# nintendo-hid.net
KiCad netlist of a schematic drawn in EAGLE
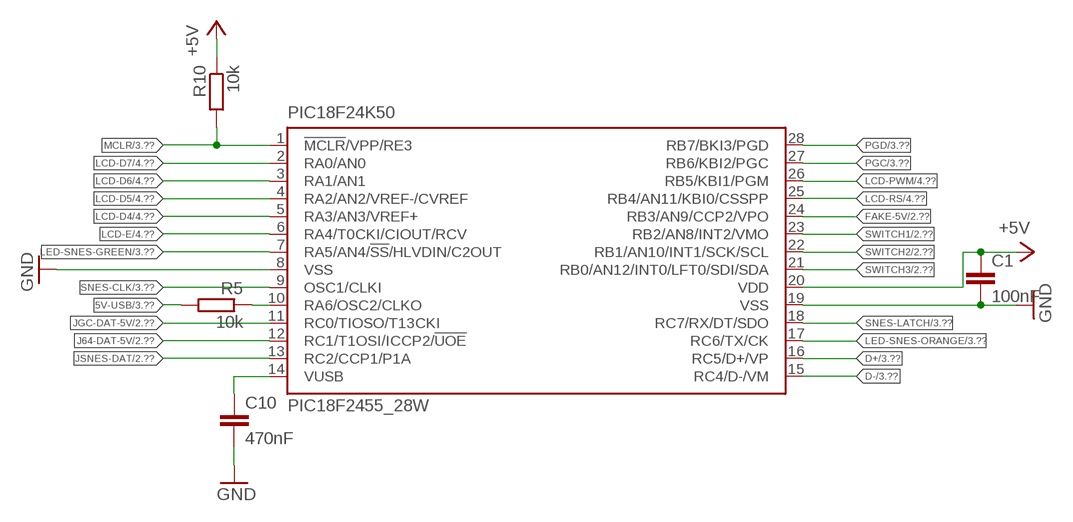
[diagram p0: schematic, sheet 1]
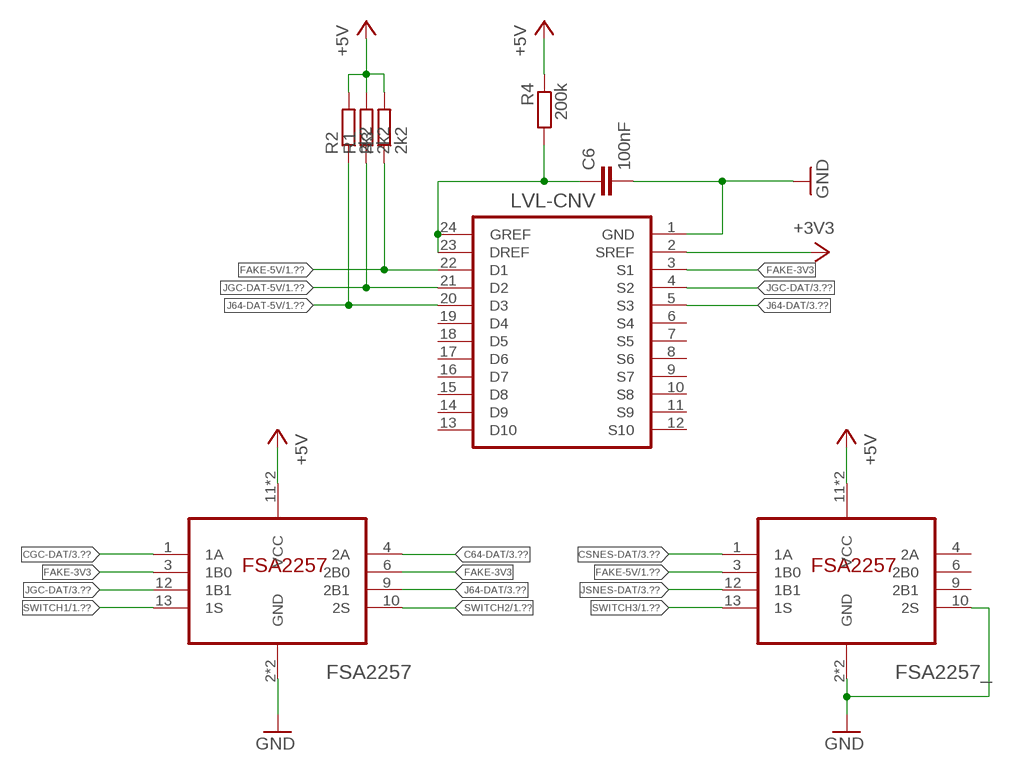
[diagram p1: schematic, sheet 2]
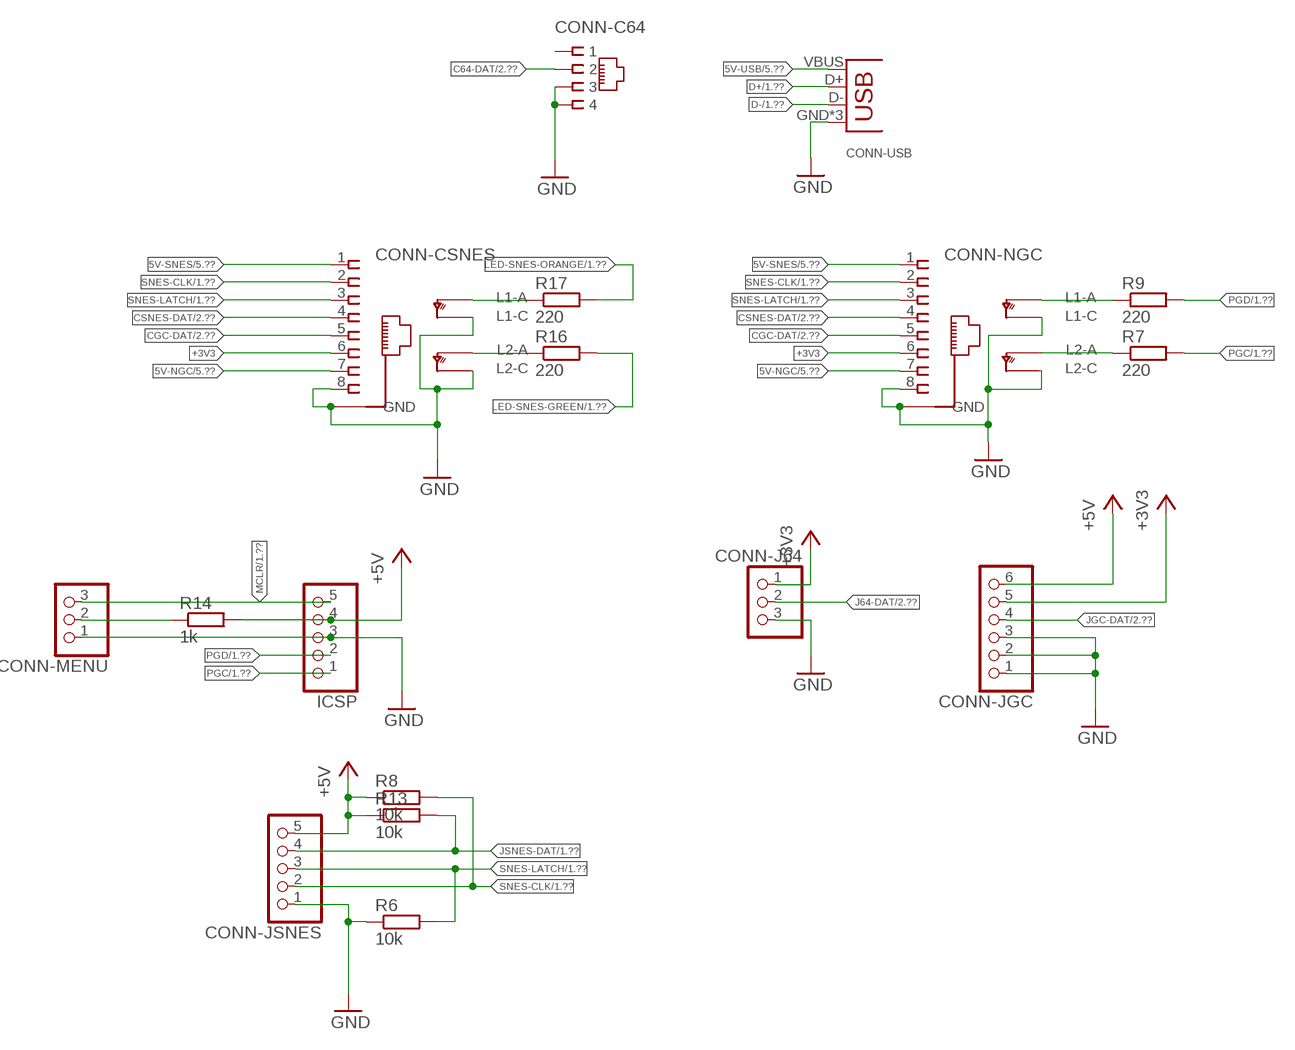
[diagram p2: schematic, sheet 3]
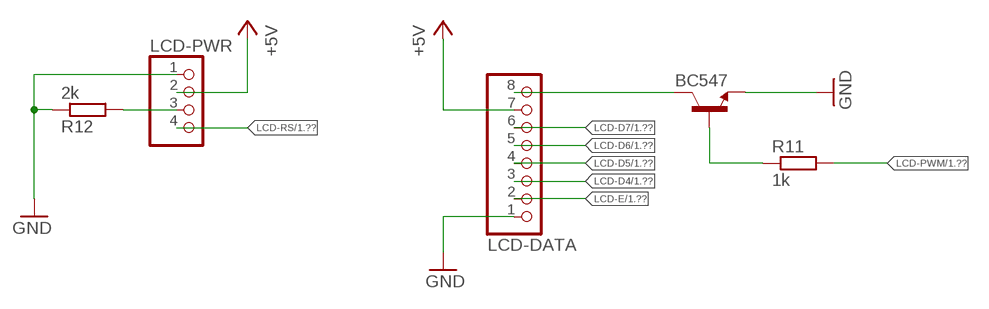
[diagram p3: schematic, sheet 4]
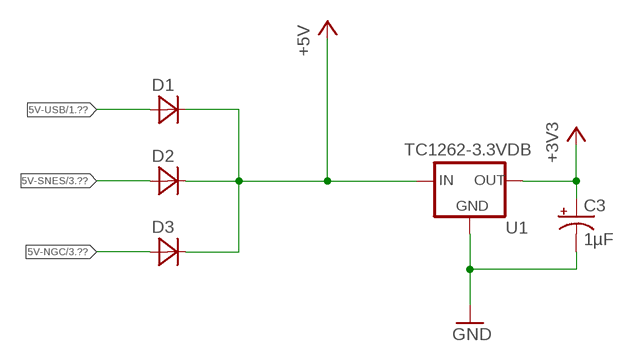
[diagram p4: schematic, sheet 5]

(export (version "E")
  (design (tool "Eeschema 10.0.6"))
  (components
    (comp (ref "CONN-C64")
      (value "RJ11-6P4C")
      (footprint "eagle-import:RJ11-4C")
      (libsource (lib "eagle-import") (part "RJ11-6P4C"))
    )
    (comp (ref "CONN-CSNES")
      (value "RJ45-NIELS")
      (footprint "eagle-import:RJ45-NIELS")
      (libsource (lib "eagle-import") (part "RJ45-NIELS"))
    )
    (comp (ref "CONN-J64")
      (value "PINHD-1X3")
      (footprint "eagle-import:1X03")
      (libsource (lib "eagle-import") (part "PINHD-1X3"))
    )
    (comp (ref "CONN-JGC")
      (value "PINHD-1X6")
      (footprint "eagle-import:1X06")
      (libsource (lib "eagle-import") (part "PINHD-1X6"))
    )
    (comp (ref "CONN-JSNES")
      (value "PINHD-1X5")
      (footprint "eagle-import:1X05")
      (libsource (lib "eagle-import") (part "PINHD-1X5"))
    )
    (comp (ref "CONN-MENU")
      (value "PINHD-1X3")
      (footprint "eagle-import:1X03")
      (libsource (lib "eagle-import") (part "PINHD-1X3"))
    )
    (comp (ref "CONN-NGC")
      (value "RJ45-NIELS")
      (footprint "eagle-import:RJ45-NIELS")
      (libsource (lib "eagle-import") (part "RJ45-NIELS"))
    )
    (comp (ref "CONN-USB")
      (value "USB-B-NIELS")
      (footprint "eagle-import:USB-B-H")
      (libsource (lib "eagle-import") (part "USB-B-NIELS"))
    )
    (comp (ref "ICSP")
      (value "PINHD-1X5")
      (footprint "eagle-import:1X05")
      (libsource (lib "eagle-import") (part "PINHD-1X5"))
    )
    (comp (ref "R6")
      (value "10k")
      (footprint "eagle-import:R0603")
      (libsource (lib "eagle-import") (part "R-EU_R0603"))
    )
    (comp (ref "R7")
      (value "220")
      (footprint "eagle-import:R0603")
      (libsource (lib "eagle-import") (part "R-EU_R0603"))
    )
    (comp (ref "R8")
      (value "10k")
      (footprint "eagle-import:R0603")
      (libsource (lib "eagle-import") (part "R-EU_R0603"))
    )
    (comp (ref "R9")
      (value "220")
      (footprint "eagle-import:R0603")
      (libsource (lib "eagle-import") (part "R-EU_R0603"))
    )
    (comp (ref "R13")
      (value "10k")
      (footprint "eagle-import:R0603")
      (libsource (lib "eagle-import") (part "R-EU_R0603"))
    )
    (comp (ref "R14")
      (value "1k")
      (footprint "eagle-import:R0603")
      (libsource (lib "eagle-import") (part "R-EU_R0603"))
    )
    (comp (ref "R16")
      (value "220")
      (footprint "eagle-import:R0603")
      (libsource (lib "eagle-import") (part "R-EU_R0603"))
    )
    (comp (ref "R17")
      (value "220")
      (footprint "eagle-import:R0603")
      (libsource (lib "eagle-import") (part "R-EU_R0603"))
    )
    (comp (ref "C1")
      (value "100nF")
      (footprint "eagle-import:C0603")
      (libsource (lib "eagle-import") (part "C-EUC0603"))
    )
    (comp (ref "C10")
      (value "470nF")
      (footprint "eagle-import:C0603")
      (libsource (lib "eagle-import") (part "C-EUC0603"))
    )
    (comp (ref "PIC18F24K50")
      (value "PIC18F2455_28W")
      (footprint "eagle-import:SO28W")
      (fields (field (name "MF") "MICROCHIP") (field (name "MPN") "PIC18F2455-I/SO"))
      (libsource (lib "eagle-import") (part "PIC18F2_28W455"))
    )
    (comp (ref "R5")
      (value "10k")
      (footprint "eagle-import:R0603")
      (libsource (lib "eagle-import") (part "R-EU_R0603"))
    )
    (comp (ref "R10")
      (value "10k")
      (footprint "eagle-import:R0603")
      (libsource (lib "eagle-import") (part "R-EU_R0603"))
    )
    (comp (ref "BC547")
      (value "BC547")
      (footprint "eagle-import:TO92")
      (libsource (lib "eagle-import") (part "BC547"))
    )
    (comp (ref "LCD-DATA")
      (value "PINHD-1X8")
      (footprint "eagle-import:1X08")
      (libsource (lib "eagle-import") (part "PINHD-1X8"))
    )
    (comp (ref "LCD-PWR")
      (value "PINHD-1X4")
      (footprint "eagle-import:1X04")
      (libsource (lib "eagle-import") (part "PINHD-1X4"))
    )
    (comp (ref "R11")
      (value "1k")
      (footprint "eagle-import:R0603")
      (libsource (lib "eagle-import") (part "R-EU_R0603"))
    )
    (comp (ref "R12")
      (value "2k")
      (footprint "eagle-import:R0603")
      (libsource (lib "eagle-import") (part "R-EU_R0603"))
    )
    (comp (ref "C6")
      (value "100nF")
      (footprint "eagle-import:C0603")
      (libsource (lib "eagle-import") (part "C-EUC0603"))
    )
    (comp (ref "FSA2257")
      (value "FSA2257MTCX")
      (footprint "eagle-import:TSSOP14")
      (libsource (lib "eagle-import") (part "FSA2257MTCX"))
    )
    (comp (ref "FSA2257_")
      (value "FSA2257MTCX")
      (footprint "eagle-import:TSSOP14")
      (libsource (lib "eagle-import") (part "FSA2257MTCX"))
    )
    (comp (ref "LVL-CNV")
      (value "GTL2010")
      (footprint "eagle-import:TSSOP24")
      (libsource (lib "eagle-import") (part "GTL2010"))
    )
    (comp (ref "R1")
      (value "2k2")
      (footprint "eagle-import:R0603")
      (libsource (lib "eagle-import") (part "R-EU_R0603"))
    )
    (comp (ref "R2")
      (value "2k2")
      (footprint "eagle-import:R0603")
      (libsource (lib "eagle-import") (part "R-EU_R0603"))
    )
    (comp (ref "R3")
      (value "2k2")
      (footprint "eagle-import:R0603")
      (libsource (lib "eagle-import") (part "R-EU_R0603"))
    )
    (comp (ref "R4")
      (value "200k")
      (footprint "eagle-import:R0603")
      (libsource (lib "eagle-import") (part "R-EU_R0603"))
    )
    (comp (ref "C3")
      (value "1µF")
      (footprint "eagle-import:PANASONIC_D")
      (libsource (lib "eagle-import") (part "47UF-50V-20%(ELECT)"))
    )
    (comp (ref "D1")
      (value "MBR120VLSFT1G")
      (footprint "eagle-import:SOD123")
      (libsource (lib "eagle-import") (part "MBR120VLSFT1G"))
    )
    (comp (ref "D2")
      (value "MBR120VLSFT1G")
      (footprint "eagle-import:SOD123")
      (libsource (lib "eagle-import") (part "MBR120VLSFT1G"))
    )
    (comp (ref "D3")
      (value "MBR120VLSFT1G")
      (footprint "eagle-import:SOD123")
      (libsource (lib "eagle-import") (part "MBR120VLSFT1G"))
    )
    (comp (ref "U1")
      (value "TC1262-3.3VDB")
      (footprint "eagle-import:SOT230P700X180-4N")
      (libsource (lib "eagle-import") (part "TC1262-3.3VDB"))
    )
  )
  (nets
    (net (code "1") (name "+3V3") (class "Default")
      (node (ref "C3") (pin "+") (pinfunction "+_+") (pintype "passive"))
      (node (ref "CONN-CSNES") (pin "6") (pinfunction "6_6") (pintype "passive"))
      (node (ref "CONN-J64") (pin "1") (pinfunction "1_1") (pintype "passive"))
      (node (ref "CONN-JGC") (pin "5") (pinfunction "5_5") (pintype "passive"))
      (node (ref "CONN-NGC") (pin "6") (pinfunction "6_6") (pintype "passive"))
      (node (ref "LVL-CNV") (pin "2") (pinfunction "SREF_2") (pintype "power_in"))
      (node (ref "U1") (pin "3") (pinfunction "OUT_3") (pintype "passive"))
    )
    (net (code "2") (name "+5V") (class "Default")
      (node (ref "C1") (pin "1") (pinfunction "1_1") (pintype "passive"))
      (node (ref "CONN-JGC") (pin "6") (pinfunction "6_6") (pintype "passive"))
      (node (ref "CONN-JSNES") (pin "5") (pinfunction "5_5") (pintype "passive"))
      (node (ref "D1") (pin "1") (pinfunction "C_1") (pintype "passive"))
      (node (ref "D2") (pin "1") (pinfunction "C_1") (pintype "passive"))
      (node (ref "D3") (pin "1") (pinfunction "C_1") (pintype "passive"))
      (node (ref "FSA2257") (pin "11") (pinfunction "VCC_11") (pintype "power_in"))
      (node (ref "FSA2257") (pin "14") (pinfunction "VCC_14") (pintype "power_in"))
      (node (ref "FSA2257_") (pin "11") (pinfunction "VCC_11") (pintype "power_in"))
      (node (ref "FSA2257_") (pin "14") (pinfunction "VCC_14") (pintype "power_in"))
      (node (ref "ICSP") (pin "4") (pinfunction "4_4") (pintype "passive"))
      (node (ref "LCD-DATA") (pin "7") (pinfunction "7_7") (pintype "passive"))
      (node (ref "LCD-PWR") (pin "2") (pinfunction "2_2") (pintype "passive"))
      (node (ref "PIC18F24K50") (pin "20") (pinfunction "VDD_20") (pintype "power_in"))
      (node (ref "R1") (pin "2") (pinfunction "2_2") (pintype "passive"))
      (node (ref "R10") (pin "1") (pinfunction "1_1") (pintype "passive"))
      (node (ref "R13") (pin "1") (pinfunction "1_1") (pintype "passive"))
      (node (ref "R14") (pin "2") (pinfunction "2_2") (pintype "passive"))
      (node (ref "R2") (pin "2") (pinfunction "2_2") (pintype "passive"))
      (node (ref "R3") (pin "2") (pinfunction "2_2") (pintype "passive"))
      (node (ref "R4") (pin "1") (pinfunction "1_1") (pintype "passive"))
      (node (ref "R8") (pin "1") (pinfunction "1_1") (pintype "passive"))
      (node (ref "U1") (pin "1") (pinfunction "IN_1") (pintype "input"))
    )
    (net (code "3") (name "5V-NGC") (class "Default")
      (node (ref "CONN-CSNES") (pin "7") (pinfunction "7_7") (pintype "passive"))
      (node (ref "CONN-NGC") (pin "7") (pinfunction "7_7") (pintype "passive"))
      (node (ref "D3") (pin "2") (pinfunction "A_2") (pintype "passive"))
    )
    (net (code "4") (name "5V-SNES") (class "Default")
      (node (ref "CONN-CSNES") (pin "1") (pinfunction "1_1") (pintype "passive"))
      (node (ref "CONN-NGC") (pin "1") (pinfunction "1_1") (pintype "passive"))
      (node (ref "D2") (pin "2") (pinfunction "A_2") (pintype "passive"))
    )
    (net (code "5") (name "5V-USB") (class "Default")
      (node (ref "CONN-USB") (pin "VBUS") (pinfunction "VBUS_VBUS") (pintype "bidirectional"))
      (node (ref "D1") (pin "2") (pinfunction "A_2") (pintype "passive"))
      (node (ref "R5") (pin "2") (pinfunction "2_2") (pintype "passive"))
    )
    (net (code "6") (name "C64-DAT") (class "Default")
      (node (ref "CONN-C64") (pin "2") (pinfunction "2_2") (pintype "passive"))
      (node (ref "FSA2257") (pin "4") (pinfunction "2A_4") (pintype "bidirectional"))
    )
    (net (code "7") (name "CGC-DAT") (class "Default")
      (node (ref "CONN-CSNES") (pin "5") (pinfunction "5_5") (pintype "passive"))
      (node (ref "CONN-NGC") (pin "5") (pinfunction "5_5") (pintype "passive"))
      (node (ref "FSA2257") (pin "1") (pinfunction "1A_1") (pintype "bidirectional"))
    )
    (net (code "8") (name "CSNES-DAT") (class "Default")
      (node (ref "CONN-CSNES") (pin "4") (pinfunction "4_4") (pintype "passive"))
      (node (ref "CONN-NGC") (pin "4") (pinfunction "4_4") (pintype "passive"))
      (node (ref "FSA2257_") (pin "1") (pinfunction "1A_1") (pintype "bidirectional"))
    )
    (net (code "9") (name "D+") (class "Default")
      (node (ref "CONN-USB") (pin "D+") (pinfunction "D+_D+") (pintype "bidirectional"))
      (node (ref "PIC18F24K50") (pin "16") (pinfunction "RC5/D+/VP_16") (pintype "bidirectional"))
    )
    (net (code "10") (name "D-") (class "Default")
      (node (ref "CONN-USB") (pin "D-") (pinfunction "D-_D-") (pintype "bidirectional"))
      (node (ref "PIC18F24K50") (pin "15") (pinfunction "RC4/D-/VM_15") (pintype "bidirectional"))
    )
    (net (code "11") (name "FAKE-3V3") (class "Default")
      (node (ref "FSA2257") (pin "3") (pinfunction "1B0_3") (pintype "bidirectional"))
      (node (ref "FSA2257") (pin "6") (pinfunction "2B0_6") (pintype "bidirectional"))
      (node (ref "LVL-CNV") (pin "3") (pinfunction "S1_3") (pintype "bidirectional"))
    )
    (net (code "12") (name "FAKE-5V") (class "Default")
      (node (ref "FSA2257_") (pin "3") (pinfunction "1B0_3") (pintype "bidirectional"))
      (node (ref "LVL-CNV") (pin "22") (pinfunction "D1_22") (pintype "bidirectional"))
      (node (ref "PIC18F24K50") (pin "24") (pinfunction "RB3/AN9/CCP2/VPO_24") (pintype "bidirectional"))
      (node (ref "R3") (pin "1") (pinfunction "1_1") (pintype "passive"))
    )
    (net (code "13") (name "GND") (class "Default")
      (node (ref "BC547") (pin "1") (pinfunction "E_1") (pintype "passive"))
      (node (ref "C1") (pin "2") (pinfunction "2_2") (pintype "passive"))
      (node (ref "C10") (pin "2") (pinfunction "2_2") (pintype "passive"))
      (node (ref "C3") (pin "-") (pinfunction "-_-") (pintype "passive"))
      (node (ref "C6") (pin "2") (pinfunction "2_2") (pintype "passive"))
      (node (ref "CONN-C64") (pin "3") (pinfunction "3_3") (pintype "passive"))
      (node (ref "CONN-C64") (pin "4") (pinfunction "4_4") (pintype "passive"))
      (node (ref "CONN-CSNES") (pin "8") (pinfunction "8_8") (pintype "passive"))
      (node (ref "CONN-CSNES") (pin "GND@5") (pinfunction "GND_GND@5") (pintype "power_in"))
      (node (ref "CONN-CSNES") (pin "GND@6") (pinfunction "GND_GND@6") (pintype "power_in"))
      (node (ref "CONN-CSNES") (pin "LED-GREEN-C") (pinfunction "L2C_LED-GREEN-C") (pintype "bidirectional"))
      (node (ref "CONN-CSNES") (pin "LED-ORANGE-C") (pinfunction "L1C_LED-ORANGE-C") (pintype "bidirectional"))
      (node (ref "CONN-J64") (pin "3") (pinfunction "3_3") (pintype "passive"))
      (node (ref "CONN-JGC") (pin "1") (pinfunction "1_1") (pintype "passive"))
      (node (ref "CONN-JGC") (pin "2") (pinfunction "2_2") (pintype "passive"))
      (node (ref "CONN-JGC") (pin "3") (pinfunction "3_3") (pintype "passive"))
      (node (ref "CONN-JSNES") (pin "1") (pinfunction "1_1") (pintype "passive"))
      (node (ref "CONN-MENU") (pin "1") (pinfunction "1_1") (pintype "passive"))
      (node (ref "CONN-NGC") (pin "8") (pinfunction "8_8") (pintype "passive"))
      (node (ref "CONN-NGC") (pin "GND@5") (pinfunction "GND_GND@5") (pintype "power_in"))
      (node (ref "CONN-NGC") (pin "GND@6") (pinfunction "GND_GND@6") (pintype "power_in"))
      (node (ref "CONN-NGC") (pin "LED-GREEN-C") (pinfunction "L2C_LED-GREEN-C") (pintype "bidirectional"))
      (node (ref "CONN-NGC") (pin "LED-ORANGE-C") (pinfunction "L1C_LED-ORANGE-C") (pintype "bidirectional"))
      (node (ref "CONN-USB") (pin "GND") (pinfunction "GND_GND") (pintype "bidirectional"))
      (node (ref "CONN-USB") (pin "GND@1") (pinfunction "GND_GND@1") (pintype "bidirectional"))
      (node (ref "CONN-USB") (pin "GND@2") (pinfunction "GND_GND@2") (pintype "bidirectional"))
      (node (ref "FSA2257") (pin "2") (pinfunction "GND_2") (pintype "power_in"))
      (node (ref "FSA2257") (pin "5") (pinfunction "GND_5") (pintype "power_in"))
      (node (ref "FSA2257_") (pin "10") (pinfunction "2S_10") (pintype "input"))
      (node (ref "FSA2257_") (pin "2") (pinfunction "GND_2") (pintype "power_in"))
      (node (ref "FSA2257_") (pin "5") (pinfunction "GND_5") (pintype "power_in"))
      (node (ref "ICSP") (pin "3") (pinfunction "3_3") (pintype "passive"))
      (node (ref "LCD-DATA") (pin "1") (pinfunction "1_1") (pintype "passive"))
      (node (ref "LCD-PWR") (pin "1") (pinfunction "1_1") (pintype "passive"))
      (node (ref "LVL-CNV") (pin "1") (pinfunction "GND_1") (pintype "power_in"))
      (node (ref "PIC18F24K50") (pin "19") (pinfunction "VSS_19") (pintype "power_in"))
      (node (ref "PIC18F24K50") (pin "8") (pinfunction "VSS_8") (pintype "power_in"))
      (node (ref "R12") (pin "1") (pinfunction "1_1") (pintype "passive"))
      (node (ref "R6") (pin "1") (pinfunction "1_1") (pintype "passive"))
      (node (ref "U1") (pin "2") (pinfunction "GND_2") (pintype "input"))
      (node (ref "U1") (pin "4") (pinfunction "GND_4") (pintype "input"))
    )
    (net (code "14") (name "J64-DAT") (class "Default")
      (node (ref "CONN-J64") (pin "2") (pinfunction "2_2") (pintype "passive"))
      (node (ref "FSA2257") (pin "9") (pinfunction "2B1_9") (pintype "bidirectional"))
      (node (ref "LVL-CNV") (pin "5") (pinfunction "S3_5") (pintype "bidirectional"))
    )
    (net (code "15") (name "J64-DAT-5V") (class "Default")
      (node (ref "LVL-CNV") (pin "20") (pinfunction "D3_20") (pintype "bidirectional"))
      (node (ref "PIC18F24K50") (pin "12") (pinfunction "RC1/T1OSI/ICCP2/~{UOE}_12") (pintype "bidirectional"))
      (node (ref "R2") (pin "1") (pinfunction "1_1") (pintype "passive"))
    )
    (net (code "16") (name "JGC-DAT") (class "Default")
      (node (ref "CONN-JGC") (pin "4") (pinfunction "4_4") (pintype "passive"))
      (node (ref "FSA2257") (pin "12") (pinfunction "1B1_12") (pintype "bidirectional"))
      (node (ref "LVL-CNV") (pin "4") (pinfunction "S2_4") (pintype "bidirectional"))
    )
    (net (code "17") (name "JGC-DAT-5V") (class "Default")
      (node (ref "LVL-CNV") (pin "21") (pinfunction "D2_21") (pintype "bidirectional"))
      (node (ref "PIC18F24K50") (pin "11") (pinfunction "RC0/TIOSO/T13CKI_11") (pintype "bidirectional"))
      (node (ref "R1") (pin "1") (pinfunction "1_1") (pintype "passive"))
    )
    (net (code "18") (name "JSNES-DAT") (class "Default")
      (node (ref "CONN-JSNES") (pin "4") (pinfunction "4_4") (pintype "passive"))
      (node (ref "FSA2257_") (pin "12") (pinfunction "1B1_12") (pintype "bidirectional"))
      (node (ref "PIC18F24K50") (pin "13") (pinfunction "RC2/CCP1/P1A_13") (pintype "bidirectional"))
      (node (ref "R13") (pin "2") (pinfunction "2_2") (pintype "passive"))
    )
    (net (code "19") (name "LCD-D4") (class "Default")
      (node (ref "LCD-DATA") (pin "3") (pinfunction "3_3") (pintype "passive"))
      (node (ref "PIC18F24K50") (pin "5") (pinfunction "RA3/AN3/VREF+_5") (pintype "bidirectional"))
    )
    (net (code "20") (name "LCD-D5") (class "Default")
      (node (ref "LCD-DATA") (pin "4") (pinfunction "4_4") (pintype "passive"))
      (node (ref "PIC18F24K50") (pin "4") (pinfunction "RA2/AN2/VREF-/CVREF_4") (pintype "bidirectional"))
    )
    (net (code "21") (name "LCD-D6") (class "Default")
      (node (ref "LCD-DATA") (pin "5") (pinfunction "5_5") (pintype "passive"))
      (node (ref "PIC18F24K50") (pin "3") (pinfunction "RA1/AN1_3") (pintype "bidirectional"))
    )
    (net (code "22") (name "LCD-D7") (class "Default")
      (node (ref "LCD-DATA") (pin "6") (pinfunction "6_6") (pintype "passive"))
      (node (ref "PIC18F24K50") (pin "2") (pinfunction "RA0/AN0_2") (pintype "bidirectional"))
    )
    (net (code "23") (name "LCD-E") (class "Default")
      (node (ref "LCD-DATA") (pin "2") (pinfunction "2_2") (pintype "passive"))
      (node (ref "PIC18F24K50") (pin "6") (pinfunction "RA4/T0CKI/CIOUT/RCV_6") (pintype "bidirectional"))
    )
    (net (code "24") (name "LCD-PWM") (class "Default")
      (node (ref "PIC18F24K50") (pin "26") (pinfunction "RB5/KBI1/PGM_26") (pintype "bidirectional"))
      (node (ref "R11") (pin "2") (pinfunction "2_2") (pintype "passive"))
    )
    (net (code "25") (name "LCD-RS") (class "Default")
      (node (ref "LCD-PWR") (pin "4") (pinfunction "4_4") (pintype "passive"))
      (node (ref "PIC18F24K50") (pin "25") (pinfunction "RB4/AN11/KBI0/CSSPP_25") (pintype "bidirectional"))
    )
    (net (code "26") (name "LED-SNES-GREEN") (class "Default")
      (node (ref "PIC18F24K50") (pin "7") (pinfunction "RA5/AN4/~{SS}/HLVDIN/C2OUT_7") (pintype "bidirectional"))
      (node (ref "R16") (pin "2") (pinfunction "2_2") (pintype "passive"))
    )
    (net (code "27") (name "LED-SNES-ORANGE") (class "Default")
      (node (ref "PIC18F24K50") (pin "17") (pinfunction "RC6/TX/CK_17") (pintype "bidirectional"))
      (node (ref "R17") (pin "2") (pinfunction "2_2") (pintype "passive"))
    )
    (net (code "28") (name "MCLR") (class "Default")
      (node (ref "CONN-MENU") (pin "3") (pinfunction "3_3") (pintype "passive"))
      (node (ref "ICSP") (pin "5") (pinfunction "5_5") (pintype "passive"))
      (node (ref "PIC18F24K50") (pin "1") (pinfunction "~{MCLR}/VPP/RE3_1") (pintype "input"))
      (node (ref "R10") (pin "2") (pinfunction "2_2") (pintype "passive"))
    )
    (net (code "29") (name "Net-(BC547-B)") (class "Default")
      (node (ref "BC547") (pin "2") (pinfunction "B_2") (pintype "passive"))
      (node (ref "R11") (pin "1") (pinfunction "1_1") (pintype "passive"))
    )
    (net (code "30") (name "Net-(BC547-C)") (class "Default")
      (node (ref "BC547") (pin "3") (pinfunction "C_3") (pintype "passive"))
      (node (ref "LCD-DATA") (pin "8") (pinfunction "8_8") (pintype "passive"))
    )
    (net (code "31") (name "Net-(CONN-CSNES-L1A)") (class "Default")
      (node (ref "CONN-CSNES") (pin "LED-ORANGE-A") (pinfunction "L1A_LED-ORANGE-A") (pintype "bidirectional"))
      (node (ref "R17") (pin "1") (pinfunction "1_1") (pintype "passive"))
    )
    (net (code "32") (name "Net-(CONN-CSNES-L2A)") (class "Default")
      (node (ref "CONN-CSNES") (pin "LED-GREEN-A") (pinfunction "L2A_LED-GREEN-A") (pintype "bidirectional"))
      (node (ref "R16") (pin "1") (pinfunction "1_1") (pintype "passive"))
    )
    (net (code "33") (name "Net-(CONN-MENU-Pad2)") (class "Default")
      (node (ref "CONN-MENU") (pin "2") (pinfunction "2_2") (pintype "passive"))
      (node (ref "R14") (pin "1") (pinfunction "1_1") (pintype "passive"))
    )
    (net (code "34") (name "Net-(CONN-NGC-L1A)") (class "Default")
      (node (ref "CONN-NGC") (pin "LED-ORANGE-A") (pinfunction "L1A_LED-ORANGE-A") (pintype "bidirectional"))
      (node (ref "R9") (pin "1") (pinfunction "1_1") (pintype "passive"))
    )
    (net (code "35") (name "Net-(CONN-NGC-L2A)") (class "Default")
      (node (ref "CONN-NGC") (pin "LED-GREEN-A") (pinfunction "L2A_LED-GREEN-A") (pintype "bidirectional"))
      (node (ref "R7") (pin "1") (pinfunction "1_1") (pintype "passive"))
    )
    (net (code "36") (name "Net-(LCD-PWR-Pad3)") (class "Default")
      (node (ref "LCD-PWR") (pin "3") (pinfunction "3_3") (pintype "passive"))
      (node (ref "R12") (pin "2") (pinfunction "2_2") (pintype "passive"))
    )
    (net (code "37") (name "Net-(LVL-CNV-DREF)") (class "Default")
      (node (ref "C6") (pin "1") (pinfunction "1_1") (pintype "passive"))
      (node (ref "LVL-CNV") (pin "23") (pinfunction "DREF_23") (pintype "power_in"))
      (node (ref "LVL-CNV") (pin "24") (pinfunction "GREF_24") (pintype "passive"))
      (node (ref "R4") (pin "2") (pinfunction "2_2") (pintype "passive"))
    )
    (net (code "38") (name "Net-(PIC18F24K50-RA6{slash}OSC2{slash}CLKO)") (class "Default")
      (node (ref "PIC18F24K50") (pin "10") (pinfunction "RA6/OSC2/CLKO_10") (pintype "output"))
      (node (ref "R5") (pin "1") (pinfunction "1_1") (pintype "passive"))
    )
    (net (code "39") (name "Net-(PIC18F24K50-VUSB)") (class "Default")
      (node (ref "C10") (pin "1") (pinfunction "1_1") (pintype "passive"))
      (node (ref "PIC18F24K50") (pin "14") (pinfunction "VUSB_14") (pintype "bidirectional"))
    )
    (net (code "40") (name "PGC") (class "Default")
      (node (ref "ICSP") (pin "1") (pinfunction "1_1") (pintype "passive"))
      (node (ref "PIC18F24K50") (pin "27") (pinfunction "RB6/KBI2/PGC_27") (pintype "bidirectional"))
      (node (ref "R7") (pin "2") (pinfunction "2_2") (pintype "passive"))
    )
    (net (code "41") (name "PGD") (class "Default")
      (node (ref "ICSP") (pin "2") (pinfunction "2_2") (pintype "passive"))
      (node (ref "PIC18F24K50") (pin "28") (pinfunction "RB7/BKI3/PGD_28") (pintype "bidirectional"))
      (node (ref "R9") (pin "2") (pinfunction "2_2") (pintype "passive"))
    )
    (net (code "42") (name "SNES-CLK") (class "Default")
      (node (ref "CONN-CSNES") (pin "2") (pinfunction "2_2") (pintype "passive"))
      (node (ref "CONN-JSNES") (pin "2") (pinfunction "2_2") (pintype "passive"))
      (node (ref "CONN-NGC") (pin "2") (pinfunction "2_2") (pintype "passive"))
      (node (ref "PIC18F24K50") (pin "9") (pinfunction "OSC1/CLKI_9") (pintype "input"))
      (node (ref "R8") (pin "2") (pinfunction "2_2") (pintype "passive"))
    )
    (net (code "43") (name "SNES-LATCH") (class "Default")
      (node (ref "CONN-CSNES") (pin "3") (pinfunction "3_3") (pintype "passive"))
      (node (ref "CONN-JSNES") (pin "3") (pinfunction "3_3") (pintype "passive"))
      (node (ref "CONN-NGC") (pin "3") (pinfunction "3_3") (pintype "passive"))
      (node (ref "PIC18F24K50") (pin "18") (pinfunction "RC7/RX/DT/SDO_18") (pintype "bidirectional"))
      (node (ref "R6") (pin "2") (pinfunction "2_2") (pintype "passive"))
    )
    (net (code "44") (name "SWITCH1") (class "Default")
      (node (ref "FSA2257") (pin "13") (pinfunction "1S_13") (pintype "input"))
      (node (ref "PIC18F24K50") (pin "23") (pinfunction "RB2/AN8/INT2/VMO_23") (pintype "bidirectional"))
    )
    (net (code "45") (name "SWITCH2") (class "Default")
      (node (ref "FSA2257") (pin "10") (pinfunction "2S_10") (pintype "input"))
      (node (ref "PIC18F24K50") (pin "22") (pinfunction "RB1/AN10/INT1/SCK/SCL_22") (pintype "bidirectional"))
    )
    (net (code "46") (name "SWITCH3") (class "Default")
      (node (ref "FSA2257_") (pin "13") (pinfunction "1S_13") (pintype "input"))
      (node (ref "PIC18F24K50") (pin "21") (pinfunction "RB0/AN12/INT0/LFT0/SDI/SDA_21") (pintype "bidirectional"))
    )
    (net (code "47") (name "unconnected-(CONN-C64-Pad1)") (class "Default")
      (node (ref "CONN-C64") (pin "1") (pinfunction "1_1") (pintype "passive"))
    )
    (net (code "48") (name "unconnected-(FSA2257_-2A-Pad4)") (class "Default")
      (node (ref "FSA2257_") (pin "4") (pinfunction "2A_4") (pintype "bidirectional"))
    )
    (net (code "49") (name "unconnected-(FSA2257_-2B0-Pad6)") (class "Default")
      (node (ref "FSA2257_") (pin "6") (pinfunction "2B0_6") (pintype "bidirectional"))
    )
    (net (code "50") (name "unconnected-(FSA2257_-2B1-Pad9)") (class "Default")
      (node (ref "FSA2257_") (pin "9") (pinfunction "2B1_9") (pintype "bidirectional"))
    )
    (net (code "51") (name "unconnected-(LVL-CNV-D4-Pad19)") (class "Default")
      (node (ref "LVL-CNV") (pin "19") (pinfunction "D4_19") (pintype "bidirectional"))
    )
    (net (code "52") (name "unconnected-(LVL-CNV-D5-Pad18)") (class "Default")
      (node (ref "LVL-CNV") (pin "18") (pinfunction "D5_18") (pintype "bidirectional"))
    )
    (net (code "53") (name "unconnected-(LVL-CNV-D6-Pad17)") (class "Default")
      (node (ref "LVL-CNV") (pin "17") (pinfunction "D6_17") (pintype "bidirectional"))
    )
    (net (code "54") (name "unconnected-(LVL-CNV-D7-Pad16)") (class "Default")
      (node (ref "LVL-CNV") (pin "16") (pinfunction "D7_16") (pintype "bidirectional"))
    )
    (net (code "55") (name "unconnected-(LVL-CNV-D8-Pad15)") (class "Default")
      (node (ref "LVL-CNV") (pin "15") (pinfunction "D8_15") (pintype "bidirectional"))
    )
    (net (code "56") (name "unconnected-(LVL-CNV-D9-Pad14)") (class "Default")
      (node (ref "LVL-CNV") (pin "14") (pinfunction "D9_14") (pintype "bidirectional"))
    )
    (net (code "57") (name "unconnected-(LVL-CNV-D10-Pad13)") (class "Default")
      (node (ref "LVL-CNV") (pin "13") (pinfunction "D10_13") (pintype "bidirectional"))
    )
    (net (code "58") (name "unconnected-(LVL-CNV-S4-Pad6)") (class "Default")
      (node (ref "LVL-CNV") (pin "6") (pinfunction "S4_6") (pintype "bidirectional"))
    )
    (net (code "59") (name "unconnected-(LVL-CNV-S5-Pad7)") (class "Default")
      (node (ref "LVL-CNV") (pin "7") (pinfunction "S5_7") (pintype "bidirectional"))
    )
    (net (code "60") (name "unconnected-(LVL-CNV-S6-Pad8)") (class "Default")
      (node (ref "LVL-CNV") (pin "8") (pinfunction "S6_8") (pintype "bidirectional"))
    )
    (net (code "61") (name "unconnected-(LVL-CNV-S7-Pad9)") (class "Default")
      (node (ref "LVL-CNV") (pin "9") (pinfunction "S7_9") (pintype "bidirectional"))
    )
    (net (code "62") (name "unconnected-(LVL-CNV-S8-Pad10)") (class "Default")
      (node (ref "LVL-CNV") (pin "10") (pinfunction "S8_10") (pintype "bidirectional"))
    )
    (net (code "63") (name "unconnected-(LVL-CNV-S9-Pad11)") (class "Default")
      (node (ref "LVL-CNV") (pin "11") (pinfunction "S9_11") (pintype "bidirectional"))
    )
    (net (code "64") (name "unconnected-(LVL-CNV-S10-Pad12)") (class "Default")
      (node (ref "LVL-CNV") (pin "12") (pinfunction "S10_12") (pintype "bidirectional"))
    )
  )
)
